# io.net
KiCad netlist of a schematic drawn in Altium Designer
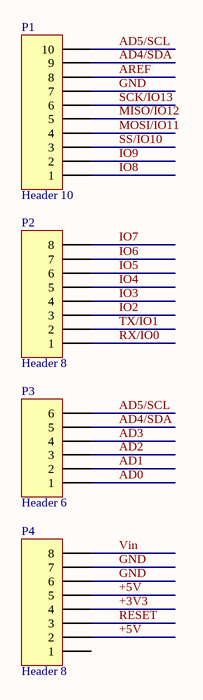
[diagram p0: io.SchDoc]

(export (version "E")
  (design (tool "Eeschema 10.0.6"))
  (components
    (comp (ref "P1")
      (value "Header 10")
      (footprint "HDR1X10")
      (description "Header, 10-Pin")
      (fields (field (name "PUBLISHER") "Altium Limited"))
      (libsource (lib "Miscellaneous Connectors") (part "Header 10"))
    )
    (comp (ref "P2")
      (value "Header 8")
      (footprint "HDR1X8")
      (description "Header, 8-Pin")
      (fields (field (name "PUBLISHER") "Altium Limited"))
      (libsource (lib "Miscellaneous Connectors") (part "Header 8"))
    )
    (comp (ref "P3")
      (value "Header 6")
      (footprint "HDR1X6")
      (description "Header, 6-Pin")
      (fields (field (name "PUBLISHER") "Altium Limited"))
      (libsource (lib "Miscellaneous Connectors") (part "Header 6"))
    )
    (comp (ref "P4")
      (value "Header 8")
      (footprint "HDR1X8")
      (description "Header, 8-Pin")
      (fields (field (name "PUBLISHER") "Altium Limited"))
      (libsource (lib "Miscellaneous Connectors") (part "Header 8"))
    )
  )
  (nets
    (net (code "1") (name "/+3V3") (class "Default")
      (node (ref "P4") (pin "4") (pinfunction "4_4") (pintype "passive"))
    )
    (net (code "2") (name "/+5V") (class "Default")
      (node (ref "P4") (pin "2") (pinfunction "2_2") (pintype "passive"))
      (node (ref "P4") (pin "5") (pinfunction "5_5") (pintype "passive"))
    )
    (net (code "3") (name "/AD0") (class "Default")
      (node (ref "P3") (pin "1") (pinfunction "1_1") (pintype "passive"))
    )
    (net (code "4") (name "/AD1") (class "Default")
      (node (ref "P3") (pin "2") (pinfunction "2_2") (pintype "passive"))
    )
    (net (code "5") (name "/AD2") (class "Default")
      (node (ref "P3") (pin "3") (pinfunction "3_3") (pintype "passive"))
    )
    (net (code "6") (name "/AD3") (class "Default")
      (node (ref "P3") (pin "4") (pinfunction "4_4") (pintype "passive"))
    )
    (net (code "7") (name "/AD4{slash}SDA") (class "Default")
      (node (ref "P1") (pin "9") (pinfunction "9_9") (pintype "passive"))
      (node (ref "P3") (pin "5") (pinfunction "5_5") (pintype "passive"))
    )
    (net (code "8") (name "/AD5{slash}SCL") (class "Default")
      (node (ref "P1") (pin "10") (pinfunction "10_10") (pintype "passive"))
      (node (ref "P3") (pin "6") (pinfunction "6_6") (pintype "passive"))
    )
    (net (code "9") (name "/AREF") (class "Default")
      (node (ref "P1") (pin "8") (pinfunction "8_8") (pintype "passive"))
    )
    (net (code "10") (name "/GND") (class "Default")
      (node (ref "P1") (pin "7") (pinfunction "7_7") (pintype "passive"))
      (node (ref "P4") (pin "6") (pinfunction "6_6") (pintype "passive"))
      (node (ref "P4") (pin "7") (pinfunction "7_7") (pintype "passive"))
    )
    (net (code "11") (name "/IO2") (class "Default")
      (node (ref "P2") (pin "3") (pinfunction "3_3") (pintype "passive"))
    )
    (net (code "12") (name "/IO3") (class "Default")
      (node (ref "P2") (pin "4") (pinfunction "4_4") (pintype "passive"))
    )
    (net (code "13") (name "/IO4") (class "Default")
      (node (ref "P2") (pin "5") (pinfunction "5_5") (pintype "passive"))
    )
    (net (code "14") (name "/IO5") (class "Default")
      (node (ref "P2") (pin "6") (pinfunction "6_6") (pintype "passive"))
    )
    (net (code "15") (name "/IO6") (class "Default")
      (node (ref "P2") (pin "7") (pinfunction "7_7") (pintype "passive"))
    )
    (net (code "16") (name "/IO7") (class "Default")
      (node (ref "P2") (pin "8") (pinfunction "8_8") (pintype "passive"))
    )
    (net (code "17") (name "/IO8") (class "Default")
      (node (ref "P1") (pin "1") (pinfunction "1_1") (pintype "passive"))
    )
    (net (code "18") (name "/IO9") (class "Default")
      (node (ref "P1") (pin "2") (pinfunction "2_2") (pintype "passive"))
    )
    (net (code "19") (name "/MISO{slash}IO12") (class "Default")
      (node (ref "P1") (pin "5") (pinfunction "5_5") (pintype "passive"))
    )
    (net (code "20") (name "/MOSI{slash}IO11") (class "Default")
      (node (ref "P1") (pin "4") (pinfunction "4_4") (pintype "passive"))
    )
    (net (code "21") (name "/RESET") (class "Default")
      (node (ref "P4") (pin "3") (pinfunction "3_3") (pintype "passive"))
    )
    (net (code "22") (name "/RX{slash}IO0") (class "Default")
      (node (ref "P2") (pin "1") (pinfunction "1_1") (pintype "passive"))
    )
    (net (code "23") (name "/SCK{slash}IO13") (class "Default")
      (node (ref "P1") (pin "6") (pinfunction "6_6") (pintype "passive"))
    )
    (net (code "24") (name "/SS{slash}IO10") (class "Default")
      (node (ref "P1") (pin "3") (pinfunction "3_3") (pintype "passive"))
    )
    (net (code "25") (name "/TX{slash}IO1") (class "Default")
      (node (ref "P2") (pin "2") (pinfunction "2_2") (pintype "passive"))
    )
    (net (code "26") (name "/Vin") (class "Default")
      (node (ref "P4") (pin "8") (pinfunction "8_8") (pintype "passive"))
    )
    (net (code "27") (name "unconnected-(P4-Pad1)") (class "Default")
      (node (ref "P4") (pin "1") (pinfunction "1_1") (pintype "passive"))
    )
  )
)
